# FPGA.net
KiCad netlist of a schematic drawn in Altium Designer
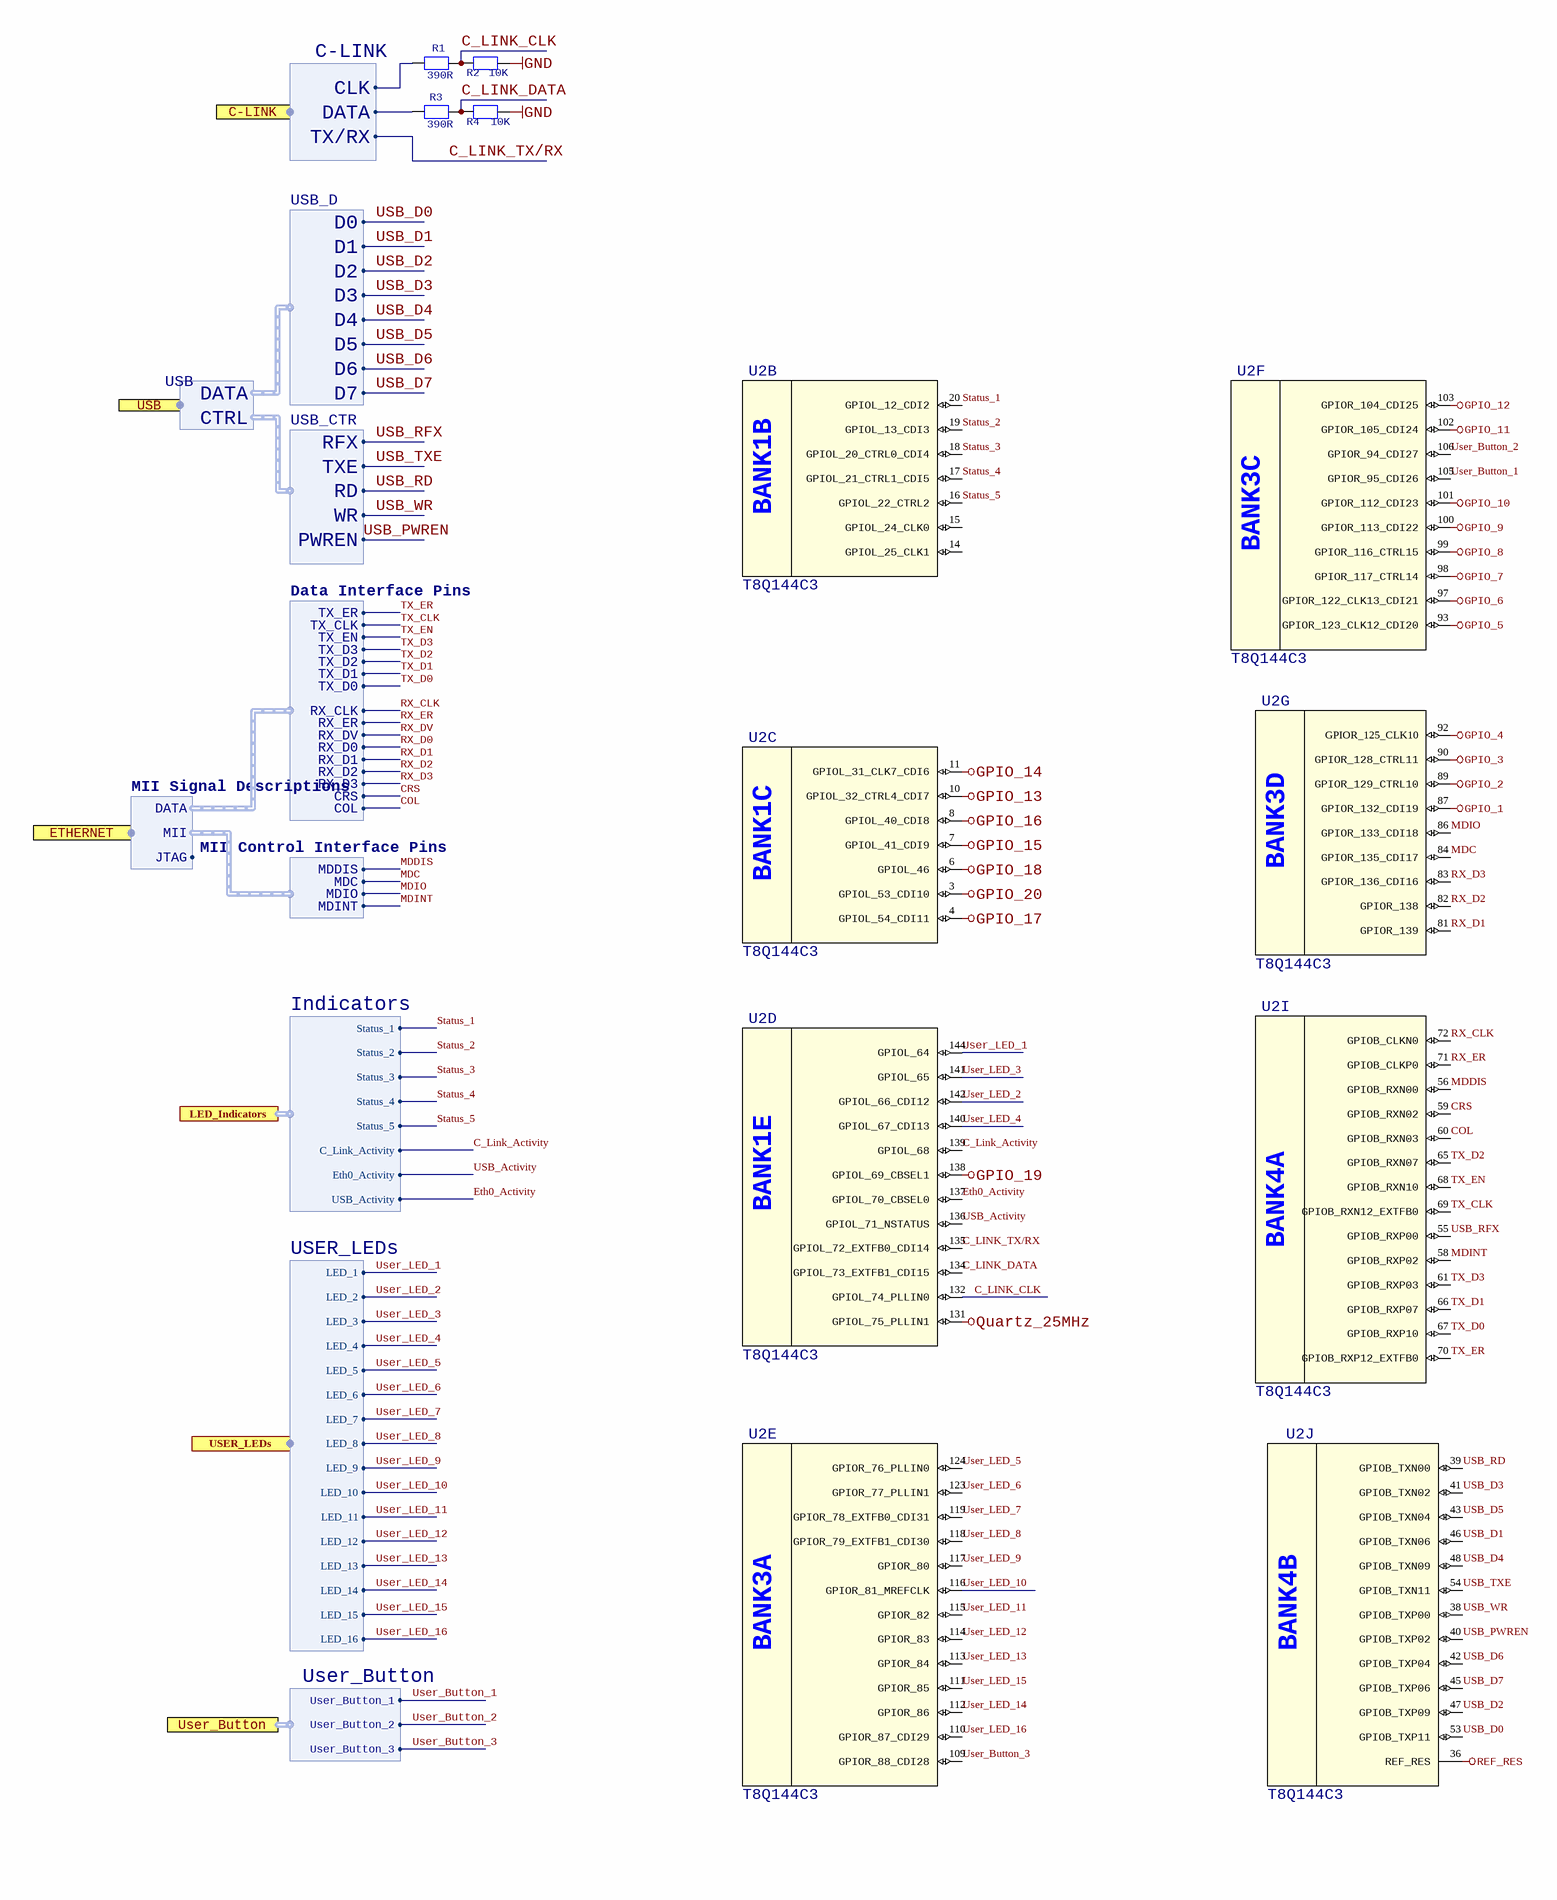
[diagram p0: FPGA.SchDoc, left]
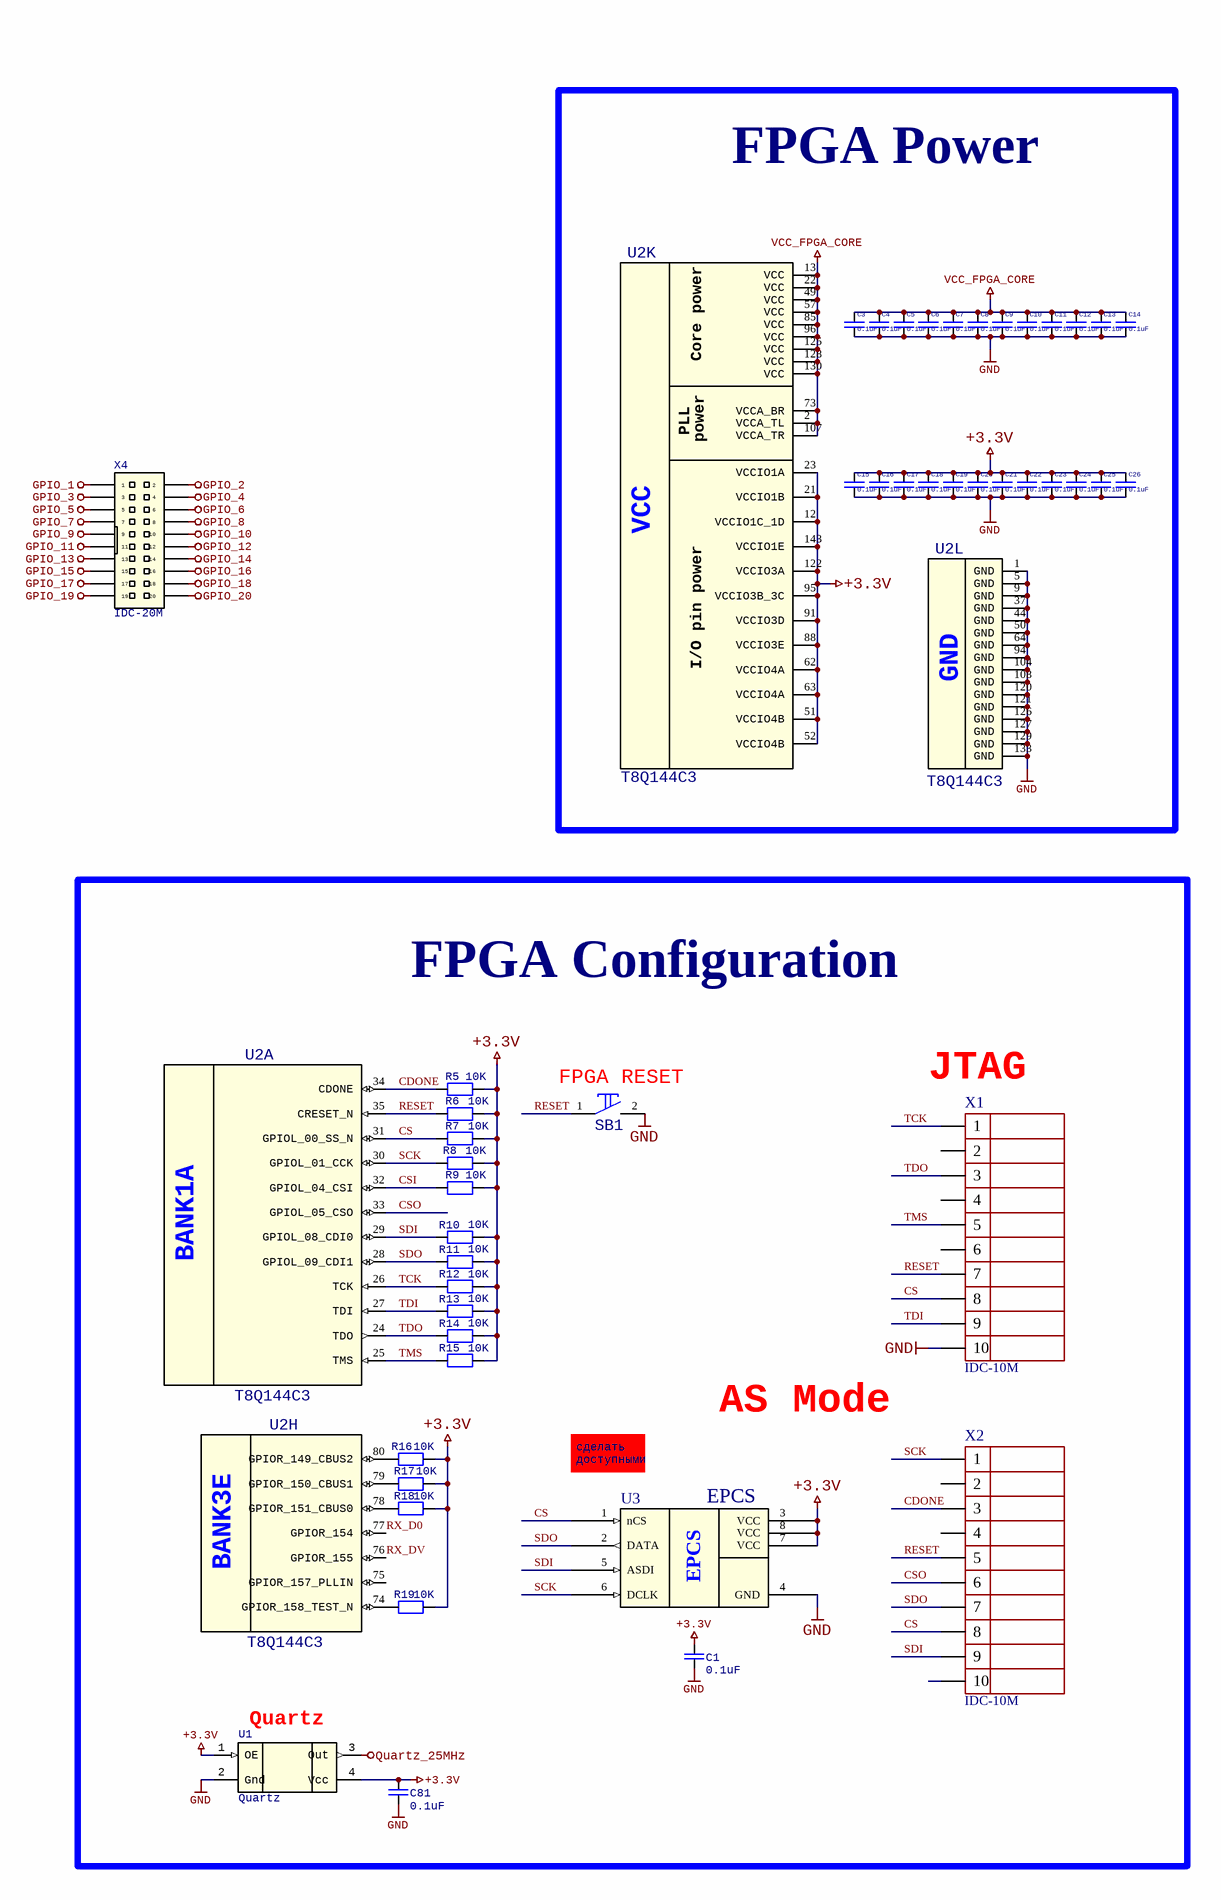
[diagram p1: FPGA.SchDoc, right]

(export (version "E")
  (design (tool "Eeschema 10.0.6"))
  (components
    (comp (ref "C1")
      (value "0.1uF")
      (footprint "Passive:C_0603")
      (description "Non-polarised capacitor")
      (libsource (lib "Passive") (part "C"))
    )
    (comp (ref "C3")
      (value "0.1uF")
      (footprint "Passive:C_0603")
      (description "Non-polarised capacitor")
      (libsource (lib "Passive") (part "C"))
    )
    (comp (ref "C4")
      (value "0.1uF")
      (footprint "Passive:C_0603")
      (description "Non-polarised capacitor")
      (libsource (lib "Passive") (part "C"))
    )
    (comp (ref "C5")
      (value "0.1uF")
      (footprint "Passive:C_0603")
      (description "Non-polarised capacitor")
      (libsource (lib "Passive") (part "C"))
    )
    (comp (ref "C6")
      (value "0.1uF")
      (footprint "Passive:C_0603")
      (description "Non-polarised capacitor")
      (libsource (lib "Passive") (part "C"))
    )
    (comp (ref "C7")
      (value "0.1uF")
      (footprint "Passive:C_0603")
      (description "Non-polarised capacitor")
      (libsource (lib "Passive") (part "C"))
    )
    (comp (ref "C8")
      (value "0.1uF")
      (footprint "Passive:C_0603")
      (description "Non-polarised capacitor")
      (libsource (lib "Passive") (part "C"))
    )
    (comp (ref "C9")
      (value "0.1uF")
      (footprint "Passive:C_0603")
      (description "Non-polarised capacitor")
      (libsource (lib "Passive") (part "C"))
    )
    (comp (ref "C10")
      (value "0.1uF")
      (footprint "Passive:C_0603")
      (description "Non-polarised capacitor")
      (libsource (lib "Passive") (part "C"))
    )
    (comp (ref "C11")
      (value "0.1uF")
      (footprint "Passive:C_0603")
      (description "Non-polarised capacitor")
      (libsource (lib "Passive") (part "C"))
    )
    (comp (ref "C12")
      (value "0.1uF")
      (footprint "Passive:C_0603")
      (description "Non-polarised capacitor")
      (libsource (lib "Passive") (part "C"))
    )
    (comp (ref "C13")
      (value "0.1uF")
      (footprint "Passive:C_0603")
      (description "Non-polarised capacitor")
      (libsource (lib "Passive") (part "C"))
    )
    (comp (ref "C14")
      (value "0.1uF")
      (footprint "Passive:C_0603")
      (description "Non-polarised capacitor")
      (libsource (lib "Passive") (part "C"))
    )
    (comp (ref "C15")
      (value "0.1uF")
      (footprint "Passive:C_0603")
      (description "Non-polarised capacitor")
      (libsource (lib "Passive") (part "C"))
    )
    (comp (ref "C16")
      (value "0.1uF")
      (footprint "Passive:C_0603")
      (description "Non-polarised capacitor")
      (libsource (lib "Passive") (part "C"))
    )
    (comp (ref "C17")
      (value "0.1uF")
      (footprint "Passive:C_0603")
      (description "Non-polarised capacitor")
      (libsource (lib "Passive") (part "C"))
    )
    (comp (ref "C18")
      (value "0.1uF")
      (footprint "Passive:C_0603")
      (description "Non-polarised capacitor")
      (libsource (lib "Passive") (part "C"))
    )
    (comp (ref "C19")
      (value "0.1uF")
      (footprint "Passive:C_0603")
      (description "Non-polarised capacitor")
      (libsource (lib "Passive") (part "C"))
    )
    (comp (ref "C20")
      (value "0.1uF")
      (footprint "Passive:C_0603")
      (description "Non-polarised capacitor")
      (libsource (lib "Passive") (part "C"))
    )
    (comp (ref "C21")
      (value "0.1uF")
      (footprint "Passive:C_0603")
      (description "Non-polarised capacitor")
      (libsource (lib "Passive") (part "C"))
    )
    (comp (ref "C22")
      (value "0.1uF")
      (footprint "Passive:C_0603")
      (description "Non-polarised capacitor")
      (libsource (lib "Passive") (part "C"))
    )
    (comp (ref "C23")
      (value "0.1uF")
      (footprint "Passive:C_0603")
      (description "Non-polarised capacitor")
      (libsource (lib "Passive") (part "C"))
    )
    (comp (ref "C24")
      (value "0.1uF")
      (footprint "Passive:C_0603")
      (description "Non-polarised capacitor")
      (libsource (lib "Passive") (part "C"))
    )
    (comp (ref "C25")
      (value "0.1uF")
      (footprint "Passive:C_0603")
      (description "Non-polarised capacitor")
      (libsource (lib "Passive") (part "C"))
    )
    (comp (ref "C26")
      (value "0.1uF")
      (footprint "Passive:C_0603")
      (description "Non-polarised capacitor")
      (libsource (lib "Passive") (part "C"))
    )
    (comp (ref "C81")
      (value "0.1uF")
      (footprint "Passive:C_0603")
      (description "Non-polarised capacitor")
      (libsource (lib "Passive") (part "C"))
    )
    (comp (ref "R1") (value "390R") (footprint "Passive:R_0603") (libsource (lib "Passive") (part "R")))
    (comp (ref "R2") (value "10K") (footprint "Passive:R_0603") (libsource (lib "Passive") (part "R")))
    (comp (ref "R3") (value "390R") (footprint "Passive:R_0603") (libsource (lib "Passive") (part "R")))
    (comp (ref "R4") (value "10K") (footprint "Passive:R_0603") (libsource (lib "Passive") (part "R")))
    (comp (ref "R5") (value "10K") (footprint "Passive:R_0603") (libsource (lib "Passive") (part "R")))
    (comp (ref "R6") (value "10K") (footprint "Passive:R_0603") (libsource (lib "Passive") (part "R")))
    (comp (ref "R7") (value "10K") (footprint "Passive:R_0603") (libsource (lib "Passive") (part "R")))
    (comp (ref "R8") (value "10K") (footprint "Passive:R_0603") (libsource (lib "Passive") (part "R")))
    (comp (ref "R9") (value "10K") (footprint "Passive:R_0603") (libsource (lib "Passive") (part "R")))
    (comp (ref "R10") (value "10K") (footprint "Passive:R_0603") (libsource (lib "Passive") (part "R")))
    (comp (ref "R11") (value "10K") (footprint "Passive:R_0603") (libsource (lib "Passive") (part "R")))
    (comp (ref "R12") (value "10K") (footprint "Passive:R_0603") (libsource (lib "Passive") (part "R")))
    (comp (ref "R13") (value "10K") (footprint "Passive:R_0603") (libsource (lib "Passive") (part "R")))
    (comp (ref "R14") (value "10K") (footprint "Passive:R_0603") (libsource (lib "Passive") (part "R")))
    (comp (ref "R15") (value "10K") (footprint "Passive:R_0603") (libsource (lib "Passive") (part "R")))
    (comp (ref "R16") (value "10K") (footprint "Passive:R_0603") (libsource (lib "Passive") (part "R")))
    (comp (ref "R17") (value "10K") (footprint "Passive:R_0603") (libsource (lib "Passive") (part "R")))
    (comp (ref "R18") (value "10K") (footprint "Passive:R_0603") (libsource (lib "Passive") (part "R")))
    (comp (ref "R19") (value "10K") (footprint "Passive:R_0603") (libsource (lib "Passive") (part "R")))
    (comp (ref "SB1")
      (value "Text")
      (footprint "Button:DTS-32")
      (fields (field (name "PUBLISHER") "Andrew Danich"))
      (libsource (lib "Passive") (part "Button"))
    )
    (comp (ref "U1")
      (value "Quartz")
      (footprint "SMD_Qz_7mmX5mm")
      (description "Crystal Oscillator (SMD)")
      (libsource (lib "Device") (part "Quartz"))
    )
    (comp (ref "U2")
      (value "T8Q144C3")
      (footprint "SMD_LQFP:LQFP- 144")
      (description "Trion T8 FPGA")
      (libsource (lib "Device") (part "Trion_T8Q144 FPGA"))
    )
    (comp (ref "U3")
      (value "EPCS")
      (footprint "Altera EPCS Configuration Device:SOIC8_N")
      (description "Serial Configuration (EPCS) Devices")
      (libsource (lib "Device") (part "EPCS"))
    )
    (comp (ref "X1") (value "IDC-10M") (footprint "IDC-10MS") (libsource (lib "Connector") (part "IDC-10M")))
    (comp (ref "X2") (value "IDC-10M") (footprint "IDC-10MS") (libsource (lib "Connector") (part "IDC-10M")))
    (comp (ref "X4")
      (value "IDC-20M")
      (footprint "Connectors_IDC:IDC-20")
      (libsource (lib "Connector") (part "IDC-20M"))
    )
  )
  (nets
    (net (code "16") (name "+3.3V") (class "Default")
      (node (ref "C1") (pin "1") (pinfunction "1_1") (pintype "passive"))
      (node (ref "C15") (pin "1") (pinfunction "1_1") (pintype "passive"))
      (node (ref "C16") (pin "1") (pinfunction "1_1") (pintype "passive"))
      (node (ref "C17") (pin "1") (pinfunction "1_1") (pintype "passive"))
      (node (ref "C18") (pin "1") (pinfunction "1_1") (pintype "passive"))
      (node (ref "C19") (pin "1") (pinfunction "1_1") (pintype "passive"))
      (node (ref "C20") (pin "1") (pinfunction "1_1") (pintype "passive"))
      (node (ref "C21") (pin "1") (pinfunction "1_1") (pintype "passive"))
      (node (ref "C22") (pin "1") (pinfunction "1_1") (pintype "passive"))
      (node (ref "C23") (pin "1") (pinfunction "1_1") (pintype "passive"))
      (node (ref "C24") (pin "1") (pinfunction "1_1") (pintype "passive"))
      (node (ref "C25") (pin "1") (pinfunction "1_1") (pintype "passive"))
      (node (ref "C26") (pin "1") (pinfunction "1_1") (pintype "passive"))
      (node (ref "C81") (pin "2") (pinfunction "2_2") (pintype "passive"))
      (node (ref "R10") (pin "2") (pinfunction "2_2") (pintype "passive"))
      (node (ref "R11") (pin "2") (pinfunction "2_2") (pintype "passive"))
      (node (ref "R12") (pin "2") (pinfunction "2_2") (pintype "passive"))
      (node (ref "R13") (pin "2") (pinfunction "2_2") (pintype "passive"))
      (node (ref "R14") (pin "2") (pinfunction "2_2") (pintype "passive"))
      (node (ref "R15") (pin "2") (pinfunction "2_2") (pintype "passive"))
      (node (ref "R16") (pin "2") (pinfunction "2_2") (pintype "passive"))
      (node (ref "R17") (pin "2") (pinfunction "2_2") (pintype "passive"))
      (node (ref "R18") (pin "2") (pinfunction "2_2") (pintype "passive"))
      (node (ref "R19") (pin "2") (pinfunction "2_2") (pintype "passive"))
      (node (ref "R5") (pin "2") (pinfunction "2_2") (pintype "passive"))
      (node (ref "R6") (pin "2") (pinfunction "2_2") (pintype "passive"))
      (node (ref "R7") (pin "2") (pinfunction "2_2") (pintype "passive"))
      (node (ref "R8") (pin "2") (pinfunction "2_2") (pintype "passive"))
      (node (ref "R9") (pin "2") (pinfunction "2_2") (pintype "passive"))
      (node (ref "U1") (pin "1") (pinfunction "OE_1") (pintype "input"))
      (node (ref "U1") (pin "4") (pinfunction "Vcc_4") (pintype "power_in"))
      (node (ref "U2") (pin "12") (pinfunction "VCCIO1C_1D_12") (pintype "passive"))
      (node (ref "U2") (pin "122") (pinfunction "VCCIO3A_122") (pintype "passive"))
      (node (ref "U2") (pin "143") (pinfunction "VCCIO1E_143") (pintype "passive"))
      (node (ref "U2") (pin "21") (pinfunction "VCCIO1B_21") (pintype "passive"))
      (node (ref "U2") (pin "23") (pinfunction "VCCIO1A_23") (pintype "passive"))
      (node (ref "U2") (pin "51") (pinfunction "VCCIO4B_51") (pintype "passive"))
      (node (ref "U2") (pin "52") (pinfunction "VCCIO4B_52") (pintype "passive"))
      (node (ref "U2") (pin "62") (pinfunction "VCCIO4A_62") (pintype "passive"))
      (node (ref "U2") (pin "63") (pinfunction "VCCIO4A_63") (pintype "passive"))
      (node (ref "U2") (pin "88") (pinfunction "VCCIO3E_88") (pintype "passive"))
      (node (ref "U2") (pin "91") (pinfunction "VCCIO3D_91") (pintype "passive"))
      (node (ref "U2") (pin "95") (pinfunction "VCCIO3B_3C_95") (pintype "passive"))
      (node (ref "U3") (pin "3") (pinfunction "VCC_3") (pintype "power_in"))
      (node (ref "U3") (pin "7") (pinfunction "VCC_7") (pintype "power_in"))
      (node (ref "U3") (pin "8") (pinfunction "VCC_8") (pintype "power_in"))
    )
    (net (code "17") (name "/CDONE") (class "Default")
      (node (ref "R5") (pin "1") (pinfunction "1_1") (pintype "passive"))
      (node (ref "U2") (pin "34") (pinfunction "CDONE_34") (pintype "bidirectional"))
      (node (ref "X2") (pin "3") (pinfunction "3_3") (pintype "passive"))
    )
    (net (code "18") (name "/CLK") (class "Default")
      (node (ref "R1") (pin "1") (pinfunction "1_1") (pintype "passive"))
    )
    (net (code "19") (name "/COL") (class "Default")
      (node (ref "U2") (pin "60") (pinfunction "GPIOB_RXN03_60") (pintype "bidirectional"))
    )
    (net (code "20") (name "/CRS") (class "Default")
      (node (ref "U2") (pin "59") (pinfunction "GPIOB_RXN02_59") (pintype "bidirectional"))
    )
    (net (code "21") (name "/CS") (class "Default")
      (node (ref "R7") (pin "1") (pinfunction "1_1") (pintype "passive"))
      (node (ref "U2") (pin "31") (pinfunction "GPIOL_00_SS_N_31") (pintype "bidirectional"))
      (node (ref "U3") (pin "1") (pinfunction "nCS_1") (pintype "input"))
      (node (ref "X1") (pin "8") (pinfunction "8_8") (pintype "passive"))
      (node (ref "X2") (pin "8") (pinfunction "8_8") (pintype "passive"))
    )
    (net (code "22") (name "/CSI") (class "Default")
      (node (ref "R9") (pin "1") (pinfunction "1_1") (pintype "passive"))
      (node (ref "U2") (pin "32") (pinfunction "GPIOL_04_CSI_32") (pintype "bidirectional"))
    )
    (net (code "23") (name "/CSO") (class "Default")
      (node (ref "U2") (pin "33") (pinfunction "GPIOL_05_CSO_33") (pintype "bidirectional"))
      (node (ref "X2") (pin "6") (pinfunction "6_6") (pintype "passive"))
    )
    (net (code "24") (name "/C_LINK_CLK") (class "Default")
      (node (ref "R1") (pin "2") (pinfunction "2_2") (pintype "passive"))
      (node (ref "R2") (pin "1") (pinfunction "1_1") (pintype "passive"))
      (node (ref "U2") (pin "132") (pinfunction "GPIOL_74_PLLIN0_132") (pintype "bidirectional"))
    )
    (net (code "25") (name "/C_LINK_DATA") (class "Default")
      (node (ref "R3") (pin "2") (pinfunction "2_2") (pintype "passive"))
      (node (ref "R4") (pin "1") (pinfunction "1_1") (pintype "passive"))
      (node (ref "U2") (pin "134") (pinfunction "GPIOL_73_EXTFB1_CDI15_134") (pintype "bidirectional"))
    )
    (net (code "26") (name "/C_LINK_TX{slash}RX") (class "Default")
      (node (ref "U2") (pin "135") (pinfunction "GPIOL_72_EXTFB0_CDI14_135") (pintype "bidirectional"))
    )
    (net (code "27") (name "/C_Link_Activity") (class "Default")
      (node (ref "U2") (pin "139") (pinfunction "GPIOL_68_139") (pintype "bidirectional"))
    )
    (net (code "29") (name "/Eth0_Activity") (class "Default")
      (node (ref "U2") (pin "137") (pinfunction "GPIOL_70_CBSEL0_137") (pintype "bidirectional"))
    )
    (net (code "30") (name "/MDC") (class "Default")
      (node (ref "U2") (pin "84") (pinfunction "GPIOR_135_CDI17_84") (pintype "bidirectional"))
    )
    (net (code "31") (name "/MDDIS") (class "Default")
      (node (ref "U2") (pin "56") (pinfunction "GPIOB_RXN00_56") (pintype "bidirectional"))
    )
    (net (code "32") (name "/MDINT") (class "Default")
      (node (ref "U2") (pin "58") (pinfunction "GPIOB_RXP02_58") (pintype "bidirectional"))
    )
    (net (code "33") (name "/MDIO") (class "Default")
      (node (ref "U2") (pin "86") (pinfunction "GPIOR_133_CDI18_86") (pintype "bidirectional"))
    )
    (net (code "34") (name "/RESET") (class "Default")
      (node (ref "R6") (pin "1") (pinfunction "1_1") (pintype "passive"))
      (node (ref "SB1") (pin "1") (pinfunction "1_1") (pintype "passive"))
      (node (ref "U2") (pin "35") (pinfunction "CRESET_N_35") (pintype "input"))
      (node (ref "X1") (pin "7") (pinfunction "7_7") (pintype "passive"))
      (node (ref "X2") (pin "5") (pinfunction "5_5") (pintype "passive"))
    )
    (net (code "35") (name "/RX_CLK") (class "Default")
      (node (ref "U2") (pin "72") (pinfunction "GPIOB_CLKN0_72") (pintype "bidirectional"))
    )
    (net (code "36") (name "/RX_D0") (class "Default")
      (node (ref "U2") (pin "77") (pinfunction "GPIOR_154_77") (pintype "bidirectional"))
    )
    (net (code "37") (name "/RX_D1") (class "Default")
      (node (ref "U2") (pin "81") (pinfunction "GPIOR_139_81") (pintype "bidirectional"))
    )
    (net (code "38") (name "/RX_D2") (class "Default")
      (node (ref "U2") (pin "82") (pinfunction "GPIOR_138_82") (pintype "bidirectional"))
    )
    (net (code "39") (name "/RX_D3") (class "Default")
      (node (ref "U2") (pin "83") (pinfunction "GPIOR_136_CDI16_83") (pintype "bidirectional"))
    )
    (net (code "40") (name "/RX_DV") (class "Default")
      (node (ref "U2") (pin "76") (pinfunction "GPIOR_155_76") (pintype "bidirectional"))
    )
    (net (code "41") (name "/RX_ER") (class "Default")
      (node (ref "U2") (pin "71") (pinfunction "GPIOB_CLKP0_71") (pintype "bidirectional"))
    )
    (net (code "42") (name "/SCK") (class "Default")
      (node (ref "R8") (pin "1") (pinfunction "1_1") (pintype "passive"))
      (node (ref "U2") (pin "30") (pinfunction "GPIOL_01_CCK_30") (pintype "bidirectional"))
      (node (ref "U3") (pin "6") (pinfunction "DCLK_6") (pintype "input"))
      (node (ref "X2") (pin "1") (pinfunction "1_1") (pintype "passive"))
    )
    (net (code "43") (name "/SDI") (class "Default")
      (node (ref "R10") (pin "1") (pinfunction "1_1") (pintype "passive"))
      (node (ref "U2") (pin "29") (pinfunction "GPIOL_08_CDI0_29") (pintype "bidirectional"))
      (node (ref "U3") (pin "5") (pinfunction "ASDI_5") (pintype "input"))
      (node (ref "X2") (pin "9") (pinfunction "9_9") (pintype "passive"))
    )
    (net (code "44") (name "/SDO") (class "Default")
      (node (ref "R11") (pin "1") (pinfunction "1_1") (pintype "passive"))
      (node (ref "U2") (pin "28") (pinfunction "GPIOL_09_CDI1_28") (pintype "bidirectional"))
      (node (ref "U3") (pin "2") (pinfunction "DATA_2") (pintype "output"))
      (node (ref "X2") (pin "7") (pinfunction "7_7") (pintype "passive"))
    )
    (net (code "45") (name "/Status_1") (class "Default")
      (node (ref "U2") (pin "20") (pinfunction "GPIOL_12_CDI2_20") (pintype "bidirectional"))
    )
    (net (code "46") (name "/Status_2") (class "Default")
      (node (ref "U2") (pin "19") (pinfunction "GPIOL_13_CDI3_19") (pintype "bidirectional"))
    )
    (net (code "47") (name "/Status_3") (class "Default")
      (node (ref "U2") (pin "18") (pinfunction "GPIOL_20_CTRL0_CDI4_18") (pintype "bidirectional"))
    )
    (net (code "48") (name "/Status_4") (class "Default")
      (node (ref "U2") (pin "17") (pinfunction "GPIOL_21_CTRL1_CDI5_17") (pintype "bidirectional"))
    )
    (net (code "49") (name "/Status_5") (class "Default")
      (node (ref "U2") (pin "16") (pinfunction "GPIOL_22_CTRL2_16") (pintype "bidirectional"))
    )
    (net (code "50") (name "/TCK") (class "Default")
      (node (ref "R12") (pin "1") (pinfunction "1_1") (pintype "passive"))
      (node (ref "U2") (pin "26") (pinfunction "TCK_26") (pintype "input"))
      (node (ref "X1") (pin "1") (pinfunction "1_1") (pintype "passive"))
    )
    (net (code "51") (name "/TDI") (class "Default")
      (node (ref "R13") (pin "1") (pinfunction "1_1") (pintype "passive"))
      (node (ref "U2") (pin "27") (pinfunction "TDI_27") (pintype "input"))
      (node (ref "X1") (pin "9") (pinfunction "9_9") (pintype "passive"))
    )
    (net (code "52") (name "/TDO") (class "Default")
      (node (ref "R14") (pin "1") (pinfunction "1_1") (pintype "passive"))
      (node (ref "U2") (pin "24") (pinfunction "TDO_24") (pintype "output"))
      (node (ref "X1") (pin "3") (pinfunction "3_3") (pintype "passive"))
    )
    (net (code "53") (name "/TMS") (class "Default")
      (node (ref "R15") (pin "1") (pinfunction "1_1") (pintype "passive"))
      (node (ref "U2") (pin "25") (pinfunction "TMS_25") (pintype "input"))
      (node (ref "X1") (pin "5") (pinfunction "5_5") (pintype "passive"))
    )
    (net (code "54") (name "/TX_CLK") (class "Default")
      (node (ref "U2") (pin "69") (pinfunction "GPIOB_RXN12_EXTFB0_69") (pintype "bidirectional"))
    )
    (net (code "55") (name "/TX_D0") (class "Default")
      (node (ref "U2") (pin "67") (pinfunction "GPIOB_RXP10_67") (pintype "bidirectional"))
    )
    (net (code "56") (name "/TX_D1") (class "Default")
      (node (ref "U2") (pin "66") (pinfunction "GPIOB_RXP07_66") (pintype "bidirectional"))
    )
    (net (code "57") (name "/TX_D2") (class "Default")
      (node (ref "U2") (pin "65") (pinfunction "GPIOB_RXN07_65") (pintype "bidirectional"))
    )
    (net (code "58") (name "/TX_D3") (class "Default")
      (node (ref "U2") (pin "61") (pinfunction "GPIOB_RXP03_61") (pintype "bidirectional"))
    )
    (net (code "59") (name "/TX_EN") (class "Default")
      (node (ref "U2") (pin "68") (pinfunction "GPIOB_RXN10_68") (pintype "bidirectional"))
    )
    (net (code "60") (name "/TX_ER") (class "Default")
      (node (ref "U2") (pin "70") (pinfunction "GPIOB_RXP12_EXTFB0_70") (pintype "bidirectional"))
    )
    (net (code "61") (name "/USB_Activity") (class "Default")
      (node (ref "U2") (pin "136") (pinfunction "GPIOL_71_NSTATUS_136") (pintype "bidirectional"))
    )
    (net (code "62") (name "/USB_D0") (class "Default")
      (node (ref "U2") (pin "53") (pinfunction "GPIOB_TXP11_53") (pintype "bidirectional"))
    )
    (net (code "63") (name "/USB_D1") (class "Default")
      (node (ref "U2") (pin "46") (pinfunction "GPIOB_TXN06_46") (pintype "bidirectional"))
    )
    (net (code "64") (name "/USB_D2") (class "Default")
      (node (ref "U2") (pin "47") (pinfunction "GPIOB_TXP09_47") (pintype "bidirectional"))
    )
    (net (code "65") (name "/USB_D3") (class "Default")
      (node (ref "U2") (pin "41") (pinfunction "GPIOB_TXN02_41") (pintype "bidirectional"))
    )
    (net (code "66") (name "/USB_D4") (class "Default")
      (node (ref "U2") (pin "48") (pinfunction "GPIOB_TXN09_48") (pintype "bidirectional"))
    )
    (net (code "67") (name "/USB_D5") (class "Default")
      (node (ref "U2") (pin "43") (pinfunction "GPIOB_TXN04_43") (pintype "bidirectional"))
    )
    (net (code "68") (name "/USB_D6") (class "Default")
      (node (ref "U2") (pin "42") (pinfunction "GPIOB_TXP04_42") (pintype "bidirectional"))
    )
    (net (code "69") (name "/USB_D7") (class "Default")
      (node (ref "U2") (pin "45") (pinfunction "GPIOB_TXP06_45") (pintype "bidirectional"))
    )
    (net (code "70") (name "/USB_PWREN") (class "Default")
      (node (ref "U2") (pin "40") (pinfunction "GPIOB_TXP02_40") (pintype "bidirectional"))
    )
    (net (code "71") (name "/USB_RD") (class "Default")
      (node (ref "U2") (pin "39") (pinfunction "GPIOB_TXN00_39") (pintype "bidirectional"))
    )
    (net (code "72") (name "/USB_RFX") (class "Default")
      (node (ref "U2") (pin "55") (pinfunction "GPIOB_RXP00_55") (pintype "bidirectional"))
    )
    (net (code "73") (name "/USB_TXE") (class "Default")
      (node (ref "U2") (pin "54") (pinfunction "GPIOB_TXN11_54") (pintype "bidirectional"))
    )
    (net (code "74") (name "/USB_WR") (class "Default")
      (node (ref "U2") (pin "38") (pinfunction "GPIOB_TXP00_38") (pintype "bidirectional"))
    )
    (net (code "76") (name "/User_Button_1") (class "Default")
      (node (ref "U2") (pin "105") (pinfunction "GPIOR_95_CDI26_105") (pintype "bidirectional"))
    )
    (net (code "77") (name "/User_Button_2") (class "Default")
      (node (ref "U2") (pin "106") (pinfunction "GPIOR_94_CDI27_106") (pintype "bidirectional"))
    )
    (net (code "78") (name "/User_Button_3") (class "Default")
      (node (ref "U2") (pin "109") (pinfunction "GPIOR_88_CDI28_109") (pintype "bidirectional"))
    )
    (net (code "79") (name "/User_LED_1") (class "Default")
      (node (ref "U2") (pin "144") (pinfunction "GPIOL_64_144") (pintype "bidirectional"))
    )
    (net (code "80") (name "/User_LED_2") (class "Default")
      (node (ref "U2") (pin "142") (pinfunction "GPIOL_66_CDI12_142") (pintype "bidirectional"))
    )
    (net (code "81") (name "/User_LED_3") (class "Default")
      (node (ref "U2") (pin "141") (pinfunction "GPIOL_65_141") (pintype "bidirectional"))
    )
    (net (code "82") (name "/User_LED_4") (class "Default")
      (node (ref "U2") (pin "140") (pinfunction "GPIOL_67_CDI13_140") (pintype "bidirectional"))
    )
    (net (code "83") (name "/User_LED_5") (class "Default")
      (node (ref "U2") (pin "124") (pinfunction "GPIOR_76_PLLIN0_124") (pintype "bidirectional"))
    )
    (net (code "84") (name "/User_LED_6") (class "Default")
      (node (ref "U2") (pin "123") (pinfunction "GPIOR_77_PLLIN1_123") (pintype "bidirectional"))
    )
    (net (code "85") (name "/User_LED_7") (class "Default")
      (node (ref "U2") (pin "119") (pinfunction "GPIOR_78_EXTFB0_CDI31_119") (pintype "bidirectional"))
    )
    (net (code "86") (name "/User_LED_8") (class "Default")
      (node (ref "U2") (pin "118") (pinfunction "GPIOR_79_EXTFB1_CDI30_118") (pintype "bidirectional"))
    )
    (net (code "87") (name "/User_LED_9") (class "Default")
      (node (ref "U2") (pin "117") (pinfunction "GPIOR_80_117") (pintype "bidirectional"))
    )
    (net (code "88") (name "/User_LED_10") (class "Default")
      (node (ref "U2") (pin "116") (pinfunction "GPIOR_81_MREFCLK_116") (pintype "bidirectional"))
    )
    (net (code "89") (name "/User_LED_11") (class "Default")
      (node (ref "U2") (pin "115") (pinfunction "GPIOR_82_115") (pintype "bidirectional"))
    )
    (net (code "90") (name "/User_LED_12") (class "Default")
      (node (ref "U2") (pin "114") (pinfunction "GPIOR_83_114") (pintype "bidirectional"))
    )
    (net (code "91") (name "/User_LED_13") (class "Default")
      (node (ref "U2") (pin "113") (pinfunction "GPIOR_84_113") (pintype "bidirectional"))
    )
    (net (code "92") (name "/User_LED_14") (class "Default")
      (node (ref "U2") (pin "112") (pinfunction "GPIOR_86_112") (pintype "bidirectional"))
    )
    (net (code "93") (name "/User_LED_15") (class "Default")
      (node (ref "U2") (pin "111") (pinfunction "GPIOR_85_111") (pintype "bidirectional"))
    )
    (net (code "94") (name "/User_LED_16") (class "Default")
      (node (ref "U2") (pin "110") (pinfunction "GPIOR_87_CDI29_110") (pintype "bidirectional"))
    )
    (net (code "103") (name "GND") (class "Default")
      (node (ref "C1") (pin "2") (pinfunction "2_2") (pintype "passive"))
      (node (ref "C10") (pin "2") (pinfunction "2_2") (pintype "passive"))
      (node (ref "C11") (pin "2") (pinfunction "2_2") (pintype "passive"))
      (node (ref "C12") (pin "2") (pinfunction "2_2") (pintype "passive"))
      (node (ref "C13") (pin "2") (pinfunction "2_2") (pintype "passive"))
      (node (ref "C14") (pin "2") (pinfunction "2_2") (pintype "passive"))
      (node (ref "C15") (pin "2") (pinfunction "2_2") (pintype "passive"))
      (node (ref "C16") (pin "2") (pinfunction "2_2") (pintype "passive"))
      (node (ref "C17") (pin "2") (pinfunction "2_2") (pintype "passive"))
      (node (ref "C18") (pin "2") (pinfunction "2_2") (pintype "passive"))
      (node (ref "C19") (pin "2") (pinfunction "2_2") (pintype "passive"))
      (node (ref "C20") (pin "2") (pinfunction "2_2") (pintype "passive"))
      (node (ref "C21") (pin "2") (pinfunction "2_2") (pintype "passive"))
      (node (ref "C22") (pin "2") (pinfunction "2_2") (pintype "passive"))
      (node (ref "C23") (pin "2") (pinfunction "2_2") (pintype "passive"))
      (node (ref "C24") (pin "2") (pinfunction "2_2") (pintype "passive"))
      (node (ref "C25") (pin "2") (pinfunction "2_2") (pintype "passive"))
      (node (ref "C26") (pin "2") (pinfunction "2_2") (pintype "passive"))
      (node (ref "C3") (pin "2") (pinfunction "2_2") (pintype "passive"))
      (node (ref "C4") (pin "2") (pinfunction "2_2") (pintype "passive"))
      (node (ref "C5") (pin "2") (pinfunction "2_2") (pintype "passive"))
      (node (ref "C6") (pin "2") (pinfunction "2_2") (pintype "passive"))
      (node (ref "C7") (pin "2") (pinfunction "2_2") (pintype "passive"))
      (node (ref "C8") (pin "2") (pinfunction "2_2") (pintype "passive"))
      (node (ref "C81") (pin "1") (pinfunction "1_1") (pintype "passive"))
      (node (ref "C9") (pin "2") (pinfunction "2_2") (pintype "passive"))
      (node (ref "R2") (pin "2") (pinfunction "2_2") (pintype "passive"))
      (node (ref "R4") (pin "2") (pinfunction "2_2") (pintype "passive"))
      (node (ref "SB1") (pin "2") (pinfunction "2_2") (pintype "passive"))
      (node (ref "U1") (pin "2") (pinfunction "Gnd_2") (pintype "power_in"))
      (node (ref "U2") (pin "1") (pinfunction "GND_1") (pintype "passive"))
      (node (ref "U2") (pin "104") (pinfunction "GND_104") (pintype "passive"))
      (node (ref "U2") (pin "108") (pinfunction "GND_108") (pintype "passive"))
      (node (ref "U2") (pin "120") (pinfunction "GND_120") (pintype "passive"))
      (node (ref "U2") (pin "121") (pinfunction "GND_121") (pintype "passive"))
      (node (ref "U2") (pin "126") (pinfunction "GND_126") (pintype "passive"))
      (node (ref "U2") (pin "127") (pinfunction "GND_127") (pintype "passive"))
      (node (ref "U2") (pin "129") (pinfunction "GND_129") (pintype "passive"))
      (node (ref "U2") (pin "133") (pinfunction "GND_133") (pintype "passive"))
      (node (ref "U2") (pin "37") (pinfunction "GND_37") (pintype "passive"))
      (node (ref "U2") (pin "44") (pinfunction "GND_44") (pintype "passive"))
      (node (ref "U2") (pin "5") (pinfunction "GND_5") (pintype "passive"))
      (node (ref "U2") (pin "50") (pinfunction "GND_50") (pintype "passive"))
      (node (ref "U2") (pin "64") (pinfunction "GND_64") (pintype "passive"))
      (node (ref "U2") (pin "9") (pinfunction "GND_9") (pintype "passive"))
      (node (ref "U2") (pin "94") (pinfunction "GND_94") (pintype "passive"))
      (node (ref "U3") (pin "4") (pinfunction "GND_4") (pintype "power_in"))
      (node (ref "X1") (pin "10") (pinfunction "10_10") (pintype "passive"))
    )
    (net (code "104") (name "GPIO_1") (class "Default")
      (node (ref "U2") (pin "87") (pinfunction "GPIOR_132_CDI19_87") (pintype "bidirectional"))
      (node (ref "X4") (pin "1") (pinfunction "1_1") (pintype "passive"))
    )
    (net (code "105") (name "GPIO_2") (class "Default")
      (node (ref "U2") (pin "89") (pinfunction "GPIOR_129_CTRL10_89") (pintype "bidirectional"))
      (node (ref "X4") (pin "2") (pinfunction "2_2") (pintype "passive"))
    )
    (net (code "106") (name "GPIO_3") (class "Default")
      (node (ref "U2") (pin "90") (pinfunction "GPIOR_128_CTRL11_90") (pintype "bidirectional"))
      (node (ref "X4") (pin "3") (pinfunction "3_3") (pintype "passive"))
    )
    (net (code "107") (name "GPIO_4") (class "Default")
      (node (ref "U2") (pin "92") (pinfunction "GPIOR_125_CLK10_92") (pintype "bidirectional"))
      (node (ref "X4") (pin "4") (pinfunction "4_4") (pintype "passive"))
    )
    (net (code "108") (name "GPIO_5") (class "Default")
      (node (ref "U2") (pin "93") (pinfunction "GPIOR_123_CLK12_CDI20_93") (pintype "bidirectional"))
      (node (ref "X4") (pin "5") (pinfunction "5_5") (pintype "passive"))
    )
    (net (code "109") (name "GPIO_6") (class "Default")
      (node (ref "U2") (pin "97") (pinfunction "GPIOR_122_CLK13_CDI21_97") (pintype "bidirectional"))
      (node (ref "X4") (pin "6") (pinfunction "6_6") (pintype "passive"))
    )
    (net (code "110") (name "GPIO_7") (class "Default")
      (node (ref "U2") (pin "98") (pinfunction "GPIOR_117_CTRL14_98") (pintype "bidirectional"))
      (node (ref "X4") (pin "7") (pinfunction "7_7") (pintype "passive"))
    )
    (net (code "111") (name "GPIO_8") (class "Default")
      (node (ref "U2") (pin "99") (pinfunction "GPIOR_116_CTRL15_99") (pintype "bidirectional"))
      (node (ref "X4") (pin "8") (pinfunction "8_8") (pintype "passive"))
    )
    (net (code "112") (name "GPIO_9") (class "Default")
      (node (ref "U2") (pin "100") (pinfunction "GPIOR_113_CDI22_100") (pintype "bidirectional"))
      (node (ref "X4") (pin "9") (pinfunction "9_9") (pintype "passive"))
    )
    (net (code "113") (name "GPIO_10") (class "Default")
      (node (ref "U2") (pin "101") (pinfunction "GPIOR_112_CDI23_101") (pintype "bidirectional"))
      (node (ref "X4") (pin "10") (pinfunction "10_10") (pintype "passive"))
    )
    (net (code "114") (name "GPIO_11") (class "Default")
      (node (ref "U2") (pin "102") (pinfunction "GPIOR_105_CDI24_102") (pintype "bidirectional"))
      (node (ref "X4") (pin "11") (pinfunction "11_11") (pintype "passive"))
    )
    (net (code "115") (name "GPIO_12") (class "Default")
      (node (ref "U2") (pin "103") (pinfunction "GPIOR_104_CDI25_103") (pintype "bidirectional"))
      (node (ref "X4") (pin "12") (pinfunction "12_12") (pintype "passive"))
    )
    (net (code "116") (name "GPIO_13") (class "Default")
      (node (ref "U2") (pin "10") (pinfunction "GPIOL_32_CTRL4_CDI7_10") (pintype "bidirectional"))
      (node (ref "X4") (pin "13") (pinfunction "13_13") (pintype "passive"))
    )
    (net (code "117") (name "GPIO_14") (class "Default")
      (node (ref "U2") (pin "11") (pinfunction "GPIOL_31_CLK7_CDI6_11") (pintype "bidirectional"))
      (node (ref "X4") (pin "14") (pinfunction "14_14") (pintype "passive"))
    )
    (net (code "118") (name "GPIO_15") (class "Default")
      (node (ref "U2") (pin "7") (pinfunction "GPIOL_41_CDI9_7") (pintype "bidirectional"))
      (node (ref "X4") (pin "15") (pinfunction "15_15") (pintype "passive"))
    )
    (net (code "119") (name "GPIO_16") (class "Default")
      (node (ref "U2") (pin "8") (pinfunction "GPIOL_40_CDI8_8") (pintype "bidirectional"))
      (node (ref "X4") (pin "16") (pinfunction "16_16") (pintype "passive"))
    )
    (net (code "120") (name "GPIO_17") (class "Default")
      (node (ref "U2") (pin "4") (pinfunction "GPIOL_54_CDI11_4") (pintype "bidirectional"))
      (node (ref "X4") (pin "17") (pinfunction "17_17") (pintype "passive"))
    )
    (net (code "121") (name "GPIO_18") (class "Default")
      (node (ref "U2") (pin "6") (pinfunction "GPIOL_46_6") (pintype "bidirectional"))
      (node (ref "X4") (pin "18") (pinfunction "18_18") (pintype "passive"))
    )
    (net (code "122") (name "GPIO_19") (class "Default")
      (node (ref "U2") (pin "138") (pinfunction "GPIOL_69_CBSEL1_138") (pintype "bidirectional"))
      (node (ref "X4") (pin "19") (pinfunction "19_19") (pintype "passive"))
    )
    (net (code "123") (name "GPIO_20") (class "Default")
      (node (ref "U2") (pin "3") (pinfunction "GPIOL_53_CDI10_3") (pintype "bidirectional"))
      (node (ref "X4") (pin "20") (pinfunction "20_20") (pintype "passive"))
    )
    (net (code "124") (name "Net-(U2H-GPIOR_149_CBUS2)") (class "Default")
      (node (ref "R16") (pin "1") (pinfunction "1_1") (pintype "passive"))
      (node (ref "U2") (pin "80") (pinfunction "GPIOR_149_CBUS2_80") (pintype "bidirectional"))
    )
    (net (code "125") (name "Net-(U2H-GPIOR_150_CBUS1)") (class "Default")
      (node (ref "R17") (pin "1") (pinfunction "1_1") (pintype "passive"))
      (node (ref "U2") (pin "79") (pinfunction "GPIOR_150_CBUS1_79") (pintype "bidirectional"))
    )
    (net (code "126") (name "Net-(U2H-GPIOR_151_CBUS0)") (class "Default")
      (node (ref "R18") (pin "1") (pinfunction "1_1") (pintype "passive"))
      (node (ref "U2") (pin "78") (pinfunction "GPIOR_151_CBUS0_78") (pintype "bidirectional"))
    )
    (net (code "127") (name "Net-(U2H-GPIOR_158_TEST_N)") (class "Default")
      (node (ref "R19") (pin "1") (pinfunction "1_1") (pintype "passive"))
      (node (ref "U2") (pin "74") (pinfunction "GPIOR_158_TEST_N_74") (pintype "bidirectional"))
    )
    (net (code "128") (name "Quartz_25MHz") (class "Default")
      (node (ref "U1") (pin "3") (pinfunction "Out_3") (pintype "output"))
      (node (ref "U2") (pin "131") (pinfunction "GPIOL_75_PLLIN1_131") (pintype "bidirectional"))
    )
    (net (code "129") (name "REF_RES") (class "Default")
      (node (ref "U2") (pin "36") (pinfunction "REF_RES_36") (pintype "passive"))
    )
    (net (code "130") (name "VCC_FPGA_CORE") (class "Default")
      (node (ref "C10") (pin "1") (pinfunction "1_1") (pintype "passive"))
      (node (ref "C11") (pin "1") (pinfunction "1_1") (pintype "passive"))
      (node (ref "C12") (pin "1") (pinfunction "1_1") (pintype "passive"))
      (node (ref "C13") (pin "1") (pinfunction "1_1") (pintype "passive"))
      (node (ref "C14") (pin "1") (pinfunction "1_1") (pintype "passive"))
      (node (ref "C3") (pin "1") (pinfunction "1_1") (pintype "passive"))
      (node (ref "C4") (pin "1") (pinfunction "1_1") (pintype "passive"))
      (node (ref "C5") (pin "1") (pinfunction "1_1") (pintype "passive"))
      (node (ref "C6") (pin "1") (pinfunction "1_1") (pintype "passive"))
      (node (ref "C7") (pin "1") (pinfunction "1_1") (pintype "passive"))
      (node (ref "C8") (pin "1") (pinfunction "1_1") (pintype "passive"))
      (node (ref "C9") (pin "1") (pinfunction "1_1") (pintype "passive"))
      (node (ref "U2") (pin "107") (pinfunction "VCCA_TR_107") (pintype "passive"))
      (node (ref "U2") (pin "125") (pinfunction "VCC_125") (pintype "passive"))
      (node (ref "U2") (pin "128") (pinfunction "VCC_128") (pintype "passive"))
      (node (ref "U2") (pin "13") (pinfunction "VCC_13") (pintype "passive"))
      (node (ref "U2") (pin "130") (pinfunction "VCC_130") (pintype "passive"))
      (node (ref "U2") (pin "2") (pinfunction "VCCA_TL_2") (pintype "passive"))
      (node (ref "U2") (pin "22") (pinfunction "VCC_22") (pintype "passive"))
      (node (ref "U2") (pin "49") (pinfunction "VCC_49") (pintype "passive"))
      (node (ref "U2") (pin "57") (pinfunction "VCC_57") (pintype "passive"))
      (node (ref "U2") (pin "73") (pinfunction "VCCA_BR_73") (pintype "passive"))
      (node (ref "U2") (pin "85") (pinfunction "VCC_85") (pintype "passive"))
      (node (ref "U2") (pin "96") (pinfunction "VCC_96") (pintype "passive"))
    )
    (net (code "131") (name "unconnected-(R3-Pad1)") (class "Default")
      (node (ref "R3") (pin "1") (pinfunction "1_1") (pintype "passive"))
    )
    (net (code "132") (name "unconnected-(U2B-GPIOL_24_CLK0-Pad15)") (class "Default")
      (node (ref "U2") (pin "15") (pinfunction "GPIOL_24_CLK0_15") (pintype "bidirectional"))
    )
    (net (code "133") (name "unconnected-(U2B-GPIOL_25_CLK1-Pad14)") (class "Default")
      (node (ref "U2") (pin "14") (pinfunction "GPIOL_25_CLK1_14") (pintype "bidirectional"))
    )
    (net (code "134") (name "unconnected-(U2H-GPIOR_157_PLLIN-Pad75)") (class "Default")
      (node (ref "U2") (pin "75") (pinfunction "GPIOR_157_PLLIN_75") (pintype "bidirectional"))
    )
    (net (code "135") (name "unconnected-(X1-Pad2)") (class "Default")
      (node (ref "X1") (pin "2") (pinfunction "2_2") (pintype "passive"))
    )
    (net (code "136") (name "unconnected-(X1-Pad4)") (class "Default")
      (node (ref "X1") (pin "4") (pinfunction "4_4") (pintype "passive"))
    )
    (net (code "137") (name "unconnected-(X1-Pad6)") (class "Default")
      (node (ref "X1") (pin "6") (pinfunction "6_6") (pintype "passive"))
    )
    (net (code "138") (name "unconnected-(X2-Pad2)") (class "Default")
      (node (ref "X2") (pin "2") (pinfunction "2_2") (pintype "passive"))
    )
    (net (code "139") (name "unconnected-(X2-Pad4)") (class "Default")
      (node (ref "X2") (pin "4") (pinfunction "4_4") (pintype "passive"))
    )
    (net (code "140") (name "unconnected-(X2-Pad10)") (class "Default")
      (node (ref "X2") (pin "10") (pinfunction "10_10") (pintype "passive"))
    )
  )
)
